# Power.net
KiCad netlist of a schematic drawn in Altium Designer
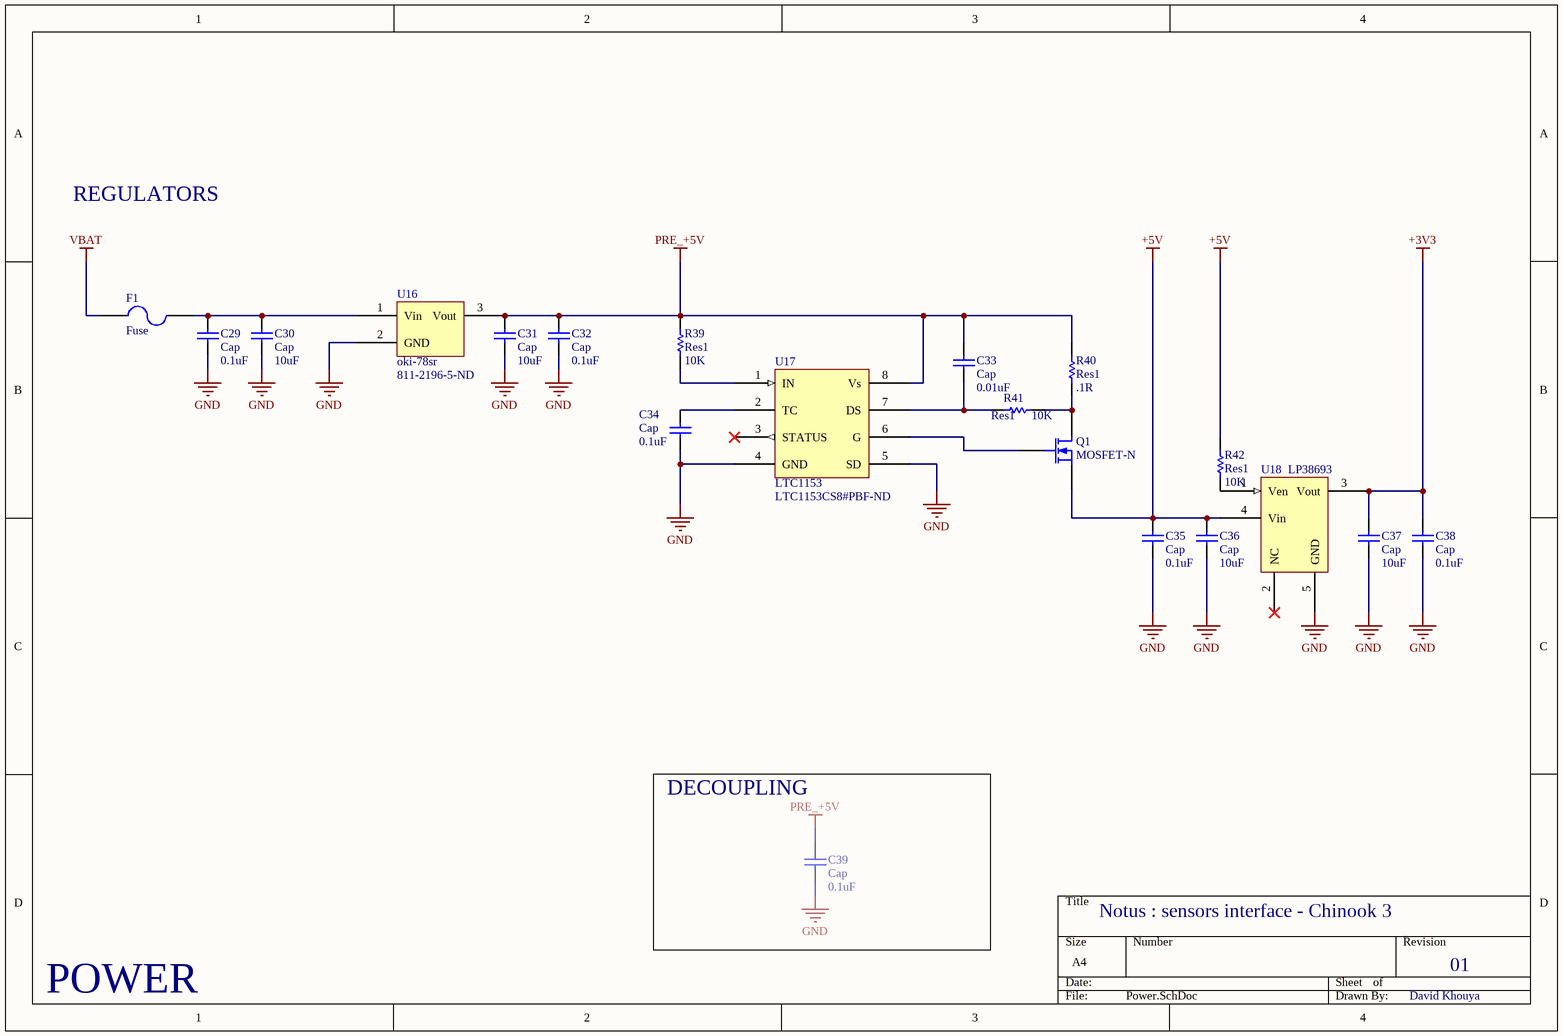
[diagram p0: Power.SchDoc]

(export (version "E")
  (design (tool "Eeschema 10.0.6"))
  (components
    (comp (ref "C29")
      (value "Cap")
      (footprint "RESC2012N")
      (description "Capacitor")
      (fields (field (name "ALTIUM_VALUE") "0.1uF") (field (name "PUBLISHER") "Altium Limited"))
      (libsource (lib "Miscellaneous Devices") (part "Cap"))
    )
    (comp (ref "C30")
      (value "Cap")
      (footprint "RESC2012N")
      (description "Capacitor")
      (fields (field (name "ALTIUM_VALUE") "10uF") (field (name "PUBLISHER") "Altium Limited"))
      (libsource (lib "Miscellaneous Devices") (part "Cap"))
    )
    (comp (ref "C31")
      (value "Cap")
      (footprint "RESC2012N")
      (description "Capacitor")
      (fields (field (name "ALTIUM_VALUE") "10uF") (field (name "PUBLISHER") "Altium Limited"))
      (libsource (lib "Miscellaneous Devices") (part "Cap"))
    )
    (comp (ref "C32")
      (value "Cap")
      (footprint "RESC2012N")
      (description "Capacitor")
      (fields (field (name "ALTIUM_VALUE") "0.1uF") (field (name "PUBLISHER") "Altium Limited"))
      (libsource (lib "Miscellaneous Devices") (part "Cap"))
    )
    (comp (ref "C33")
      (value "Cap")
      (footprint "RESC2012N")
      (description "Capacitor")
      (fields (field (name "ALTIUM_VALUE") "0.01uF") (field (name "PUBLISHER") "Altium Limited"))
      (libsource (lib "Miscellaneous Devices") (part "Cap"))
    )
    (comp (ref "C34")
      (value "Cap")
      (footprint "RESC2012N")
      (description "Capacitor")
      (fields (field (name "ALTIUM_VALUE") "0.1uF") (field (name "PUBLISHER") "Altium Limited"))
      (libsource (lib "Miscellaneous Devices") (part "Cap"))
    )
    (comp (ref "C35")
      (value "Cap")
      (footprint "RESC2012N")
      (description "Capacitor")
      (fields (field (name "ALTIUM_VALUE") "0.1uF") (field (name "PUBLISHER") "Altium Limited"))
      (libsource (lib "Miscellaneous Devices") (part "Cap"))
    )
    (comp (ref "C36")
      (value "Cap")
      (footprint "RESC2012N")
      (description "Capacitor")
      (fields (field (name "ALTIUM_VALUE") "10uF") (field (name "PUBLISHER") "Altium Limited"))
      (libsource (lib "Miscellaneous Devices") (part "Cap"))
    )
    (comp (ref "C37")
      (value "Cap")
      (footprint "RESC2012N")
      (description "Capacitor")
      (fields (field (name "ALTIUM_VALUE") "10uF") (field (name "PUBLISHER") "Altium Limited"))
      (libsource (lib "Miscellaneous Devices") (part "Cap"))
    )
    (comp (ref "C38")
      (value "Cap")
      (footprint "RESC2012N")
      (description "Capacitor")
      (fields (field (name "ALTIUM_VALUE") "0.1uF") (field (name "PUBLISHER") "Altium Limited"))
      (libsource (lib "Miscellaneous Devices") (part "Cap"))
    )
    (comp (ref "C39")
      (value "Cap")
      (footprint "RESC2012N")
      (description "Capacitor")
      (fields (field (name "ALTIUM_VALUE") "0.1uF") (field (name "PUBLISHER") "Altium Limited"))
      (libsource (lib "Miscellaneous Devices") (part "Cap"))
    )
    (comp (ref "F1")
      (value "Fuse")
      (footprint "Fuse Holder 656")
      (fields (field (name "PUBLISHER") "Altium Limited"))
      (libsource (lib "Miscellaneous Devices") (part "Fuse 2"))
    )
    (comp (ref "Q1")
      (value "MOSFET-N")
      (footprint "SOT223-4M")
      (description "N-Channel MOSFET")
      (fields (field (name "PUBLISHER") "Altium Limited"))
      (libsource (lib "Miscellaneous Devices") (part "MOSFET-N"))
    )
    (comp (ref "R39")
      (value "Res1")
      (footprint "RESC2012N")
      (description "Resistor")
      (fields (field (name "ALTIUM_VALUE") "10K") (field (name "PUBLISHER") "Altium Limited"))
      (libsource (lib "Miscellaneous Devices") (part "Res1"))
    )
    (comp (ref "R40")
      (value "Res1")
      (footprint "RESC2012N")
      (description "Resistor")
      (fields (field (name "ALTIUM_VALUE") ".1R") (field (name "PUBLISHER") "Altium Limited"))
      (libsource (lib "Miscellaneous Devices") (part "Res1"))
    )
    (comp (ref "R41")
      (value "Res1")
      (footprint "RESC2012N")
      (description "Resistor")
      (fields (field (name "ALTIUM_VALUE") "10K") (field (name "PUBLISHER") "Altium Limited"))
      (libsource (lib "Miscellaneous Devices") (part "Res1"))
    )
    (comp (ref "R42")
      (value "Res1")
      (footprint "RESC2012N")
      (description "Resistor")
      (fields (field (name "ALTIUM_VALUE") "10K") (field (name "PUBLISHER") "Altium Limited"))
      (libsource (lib "Miscellaneous Devices") (part "Res1"))
    )
    (comp (ref "U16")
      (value "oki-78sr")
      (footprint "oki-78sr")
      (description "5V 1.5A (Vin 7V-36V) swiching power supply - board mount")
      (fields (field (name "SUPPLIER PART NUMBER 1") "811-2196-5-ND"))
      (libsource (lib "dkhouya") (part "oki-78sr"))
    )
    (comp (ref "U17")
      (value "LTC1153")
      (footprint "8SOIC-2")
      (description "Over current protection - Circuit breaker")
      (fields (field (name "SUPPLIER PART NUMBER 1") "LTC1153CS8#PBF-ND"))
      (libsource (lib "dkhouya") (part "LTC1153"))
    )
    (comp (ref "U18")
      (value "LP38693")
      (footprint "SOT223-5M")
      (description "LDO 3.3V 500mA")
      (libsource (lib "dkhouya") (part "LP38693"))
    )
  )
  (nets
    (net (code "1") (name "+3V3") (class "Default")
      (node (ref "C37") (pin "2") (pinfunction "2_2") (pintype "passive"))
      (node (ref "C38") (pin "2") (pinfunction "2_2") (pintype "passive"))
      (node (ref "U18") (pin "3") (pinfunction "Vout_3") (pintype "power_in"))
    )
    (net (code "2") (name "+5V") (class "Default")
      (node (ref "C35") (pin "2") (pinfunction "2_2") (pintype "passive"))
      (node (ref "C36") (pin "2") (pinfunction "2_2") (pintype "passive"))
      (node (ref "Q1") (pin "3") (pinfunction "S_3") (pintype "passive"))
      (node (ref "R42") (pin "2") (pinfunction "2_2") (pintype "passive"))
      (node (ref "U18") (pin "4") (pinfunction "Vin_4") (pintype "passive"))
    )
    (net (code "3") (name "GND") (class "Default")
      (node (ref "C29") (pin "1") (pinfunction "1_1") (pintype "passive"))
      (node (ref "C30") (pin "1") (pinfunction "1_1") (pintype "passive"))
      (node (ref "C31") (pin "1") (pinfunction "1_1") (pintype "passive"))
      (node (ref "C32") (pin "1") (pinfunction "1_1") (pintype "passive"))
      (node (ref "C34") (pin "1") (pinfunction "1_1") (pintype "passive"))
      (node (ref "C35") (pin "1") (pinfunction "1_1") (pintype "passive"))
      (node (ref "C36") (pin "1") (pinfunction "1_1") (pintype "passive"))
      (node (ref "C37") (pin "1") (pinfunction "1_1") (pintype "passive"))
      (node (ref "C38") (pin "1") (pinfunction "1_1") (pintype "passive"))
      (node (ref "C39") (pin "1") (pinfunction "1_1") (pintype "passive"))
      (node (ref "U16") (pin "2") (pinfunction "GND_2") (pintype "power_in"))
      (node (ref "U17") (pin "4") (pinfunction "GND_4") (pintype "power_in"))
      (node (ref "U17") (pin "5") (pinfunction "SD_5") (pintype "passive"))
      (node (ref "U18") (pin "5") (pinfunction "GND_5") (pintype "power_in"))
    )
    (net (code "4") (name "Net-(Q1-D)") (class "Default")
      (node (ref "Q1") (pin "1") (pinfunction "D_1") (pintype "passive"))
      (node (ref "R40") (pin "2") (pinfunction "2_2") (pintype "passive"))
      (node (ref "R41") (pin "2") (pinfunction "2_2") (pintype "passive"))
    )
    (net (code "5") (name "Net-(Q1-G)") (class "Default")
      (node (ref "Q1") (pin "2") (pinfunction "G_2") (pintype "passive"))
      (node (ref "U17") (pin "6") (pinfunction "G_6") (pintype "passive"))
    )
    (net (code "6") (name "Net-(U16-Vin)") (class "Default")
      (node (ref "C29") (pin "2") (pinfunction "2_2") (pintype "passive"))
      (node (ref "C30") (pin "2") (pinfunction "2_2") (pintype "passive"))
      (node (ref "F1") (pin "2") (pinfunction "2_2") (pintype "passive"))
      (node (ref "U16") (pin "1") (pinfunction "Vin_1") (pintype "power_in"))
    )
    (net (code "7") (name "Net-(U17-DS)") (class "Default")
      (node (ref "C33") (pin "1") (pinfunction "1_1") (pintype "passive"))
      (node (ref "R41") (pin "1") (pinfunction "1_1") (pintype "passive"))
      (node (ref "U17") (pin "7") (pinfunction "DS_7") (pintype "passive"))
    )
    (net (code "8") (name "Net-(U17-IN)") (class "Default")
      (node (ref "R39") (pin "1") (pinfunction "1_1") (pintype "passive"))
      (node (ref "U17") (pin "1") (pinfunction "IN_1") (pintype "input"))
    )
    (net (code "9") (name "Net-(U17-TC)") (class "Default")
      (node (ref "C34") (pin "2") (pinfunction "2_2") (pintype "passive"))
      (node (ref "U17") (pin "2") (pinfunction "TC_2") (pintype "passive"))
    )
    (net (code "10") (name "Net-(U18-Ven)") (class "Default")
      (node (ref "R42") (pin "1") (pinfunction "1_1") (pintype "passive"))
      (node (ref "U18") (pin "1") (pinfunction "Ven_1") (pintype "input"))
    )
    (net (code "11") (name "PRE_+5V") (class "Default")
      (node (ref "C31") (pin "2") (pinfunction "2_2") (pintype "passive"))
      (node (ref "C32") (pin "2") (pinfunction "2_2") (pintype "passive"))
      (node (ref "C33") (pin "2") (pinfunction "2_2") (pintype "passive"))
      (node (ref "C39") (pin "2") (pinfunction "2_2") (pintype "passive"))
      (node (ref "R39") (pin "2") (pinfunction "2_2") (pintype "passive"))
      (node (ref "R40") (pin "1") (pinfunction "1_1") (pintype "passive"))
      (node (ref "U16") (pin "3") (pinfunction "Vout_3") (pintype "power_in"))
      (node (ref "U17") (pin "8") (pinfunction "Vs_8") (pintype "power_in"))
    )
    (net (code "12") (name "VBAT") (class "Default")
      (node (ref "F1") (pin "1") (pinfunction "1_1") (pintype "passive"))
    )
    (net (code "13") (name "unconnected-(U17-STATUS-Pad3)") (class "Default")
      (node (ref "U17") (pin "3") (pinfunction "STATUS_3") (pintype "output+no_connect"))
    )
    (net (code "14") (name "unconnected-(U18-NC-Pad2)") (class "Default")
      (node (ref "U18") (pin "2") (pinfunction "NC_2") (pintype "passive+no_connect"))
    )
  )
)
